# board_1.net
KiCad netlist of a schematic drawn in EAGLE
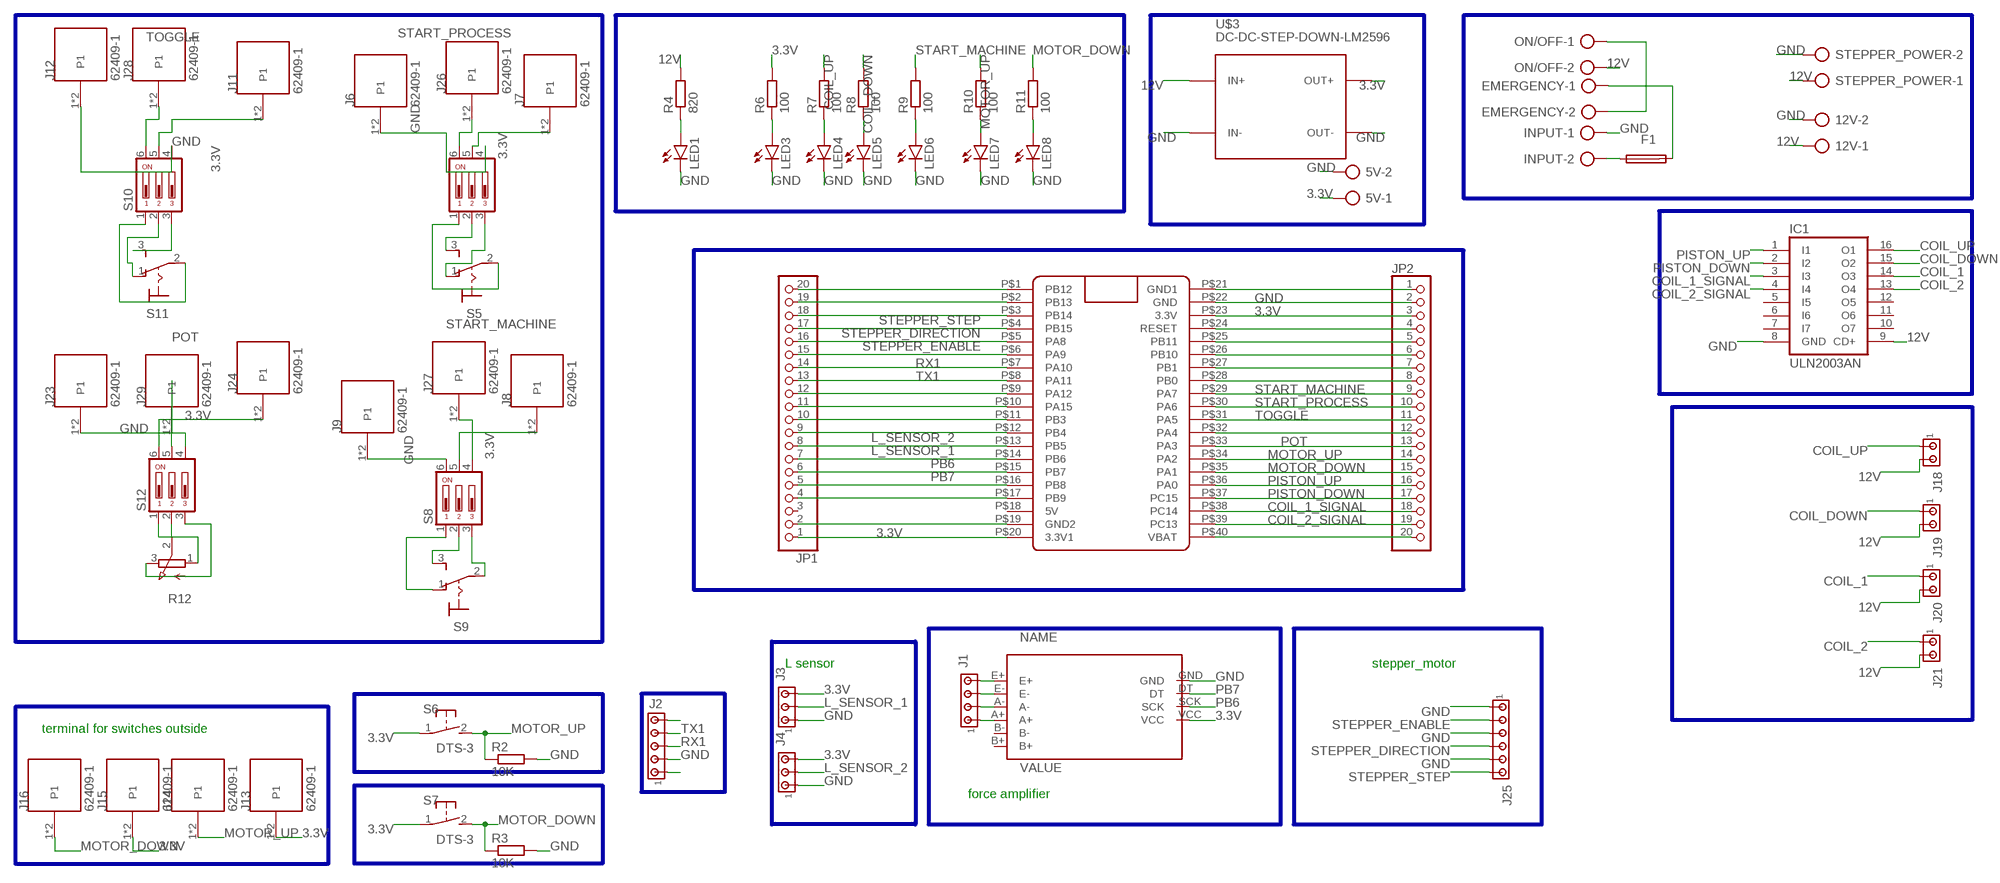
[diagram p0: schematic, sheet 1]

(export (version "E")
  (design (tool "Eeschema 10.0.6"))
  (components
    (comp (ref "5V")
      (value "AK300/2")
      (footprint "eagle-import:AK300_2")
      (libsource (lib "eagle-import") (part "AK300/2"))
    )
    (comp (ref "12V")
      (value "AK300/2")
      (footprint "eagle-import:AK300_2")
      (libsource (lib "eagle-import") (part "AK300/2"))
    )
    (comp (ref "EMERGENCY")
      (value "AK300/2")
      (footprint "eagle-import:AK300_2")
      (libsource (lib "eagle-import") (part "AK300/2"))
    )
    (comp (ref "F1")
      (value "SH22")
      (footprint "eagle-import:SH22")
      (libsource (lib "eagle-import") (part "SH22"))
    )
    (comp (ref "IC1")
      (value "ULN2003AN")
      (footprint "eagle-import:DIL16")
      (libsource (lib "eagle-import") (part "ULN2003AN"))
    )
    (comp (ref "INPUT")
      (value "AK300/2")
      (footprint "eagle-import:AK300_2")
      (libsource (lib "eagle-import") (part "AK300/2"))
    )
    (comp (ref "J1")
      (value "MTA04-100")
      (footprint "eagle-import:10X04MTA")
      (libsource (lib "eagle-import") (part "MTA04-100"))
    )
    (comp (ref "J2")
      (value "MTA05-100")
      (footprint "eagle-import:10X05MTA")
      (libsource (lib "eagle-import") (part "MTA05-100"))
    )
    (comp (ref "J3")
      (value "MTA03-100")
      (footprint "eagle-import:10X03MTA")
      (libsource (lib "eagle-import") (part "MTA03-100"))
    )
    (comp (ref "J4")
      (value "MTA03-100")
      (footprint "eagle-import:10X03MTA")
      (libsource (lib "eagle-import") (part "MTA03-100"))
    )
    (comp (ref "J6")
      (value "62409-1")
      (footprint "eagle-import:TE_62409-1")
      (fields (field (name "MF") "TE Connectivity"))
      (libsource (lib "eagle-import") (part "62409-1"))
    )
    (comp (ref "J7")
      (value "62409-1")
      (footprint "eagle-import:TE_62409-1")
      (fields (field (name "MF") "TE Connectivity"))
      (libsource (lib "eagle-import") (part "62409-1"))
    )
    (comp (ref "J8")
      (value "62409-1")
      (footprint "eagle-import:TE_62409-1")
      (fields (field (name "MF") "TE Connectivity"))
      (libsource (lib "eagle-import") (part "62409-1"))
    )
    (comp (ref "J9")
      (value "62409-1")
      (footprint "eagle-import:TE_62409-1")
      (fields (field (name "MF") "TE Connectivity"))
      (libsource (lib "eagle-import") (part "62409-1"))
    )
    (comp (ref "J11")
      (value "62409-1")
      (footprint "eagle-import:TE_62409-1")
      (fields (field (name "MF") "TE Connectivity"))
      (libsource (lib "eagle-import") (part "62409-1"))
    )
    (comp (ref "J12")
      (value "62409-1")
      (footprint "eagle-import:TE_62409-1")
      (fields (field (name "MF") "TE Connectivity"))
      (libsource (lib "eagle-import") (part "62409-1"))
    )
    (comp (ref "J13")
      (value "62409-1")
      (footprint "eagle-import:TE_62409-1")
      (fields (field (name "MF") "TE Connectivity"))
      (libsource (lib "eagle-import") (part "62409-1"))
    )
    (comp (ref "J14")
      (value "62409-1")
      (footprint "eagle-import:TE_62409-1")
      (fields (field (name "MF") "TE Connectivity"))
      (libsource (lib "eagle-import") (part "62409-1"))
    )
    (comp (ref "J15")
      (value "62409-1")
      (footprint "eagle-import:TE_62409-1")
      (fields (field (name "MF") "TE Connectivity"))
      (libsource (lib "eagle-import") (part "62409-1"))
    )
    (comp (ref "J16")
      (value "62409-1")
      (footprint "eagle-import:TE_62409-1")
      (fields (field (name "MF") "TE Connectivity"))
      (libsource (lib "eagle-import") (part "62409-1"))
    )
    (comp (ref "J18")
      (value "MTA02-100")
      (footprint "eagle-import:10X02MTA")
      (libsource (lib "eagle-import") (part "MTA02-100"))
    )
    (comp (ref "J19")
      (value "MTA02-100")
      (footprint "eagle-import:10X02MTA")
      (libsource (lib "eagle-import") (part "MTA02-100"))
    )
    (comp (ref "J20")
      (value "MTA02-100")
      (footprint "eagle-import:10X02MTA")
      (libsource (lib "eagle-import") (part "MTA02-100"))
    )
    (comp (ref "J21")
      (value "MTA02-100")
      (footprint "eagle-import:10X02MTA")
      (libsource (lib "eagle-import") (part "MTA02-100"))
    )
    (comp (ref "J23")
      (value "62409-1")
      (footprint "eagle-import:TE_62409-1")
      (fields (field (name "MF") "TE Connectivity"))
      (libsource (lib "eagle-import") (part "62409-1"))
    )
    (comp (ref "J24")
      (value "62409-1")
      (footprint "eagle-import:TE_62409-1")
      (fields (field (name "MF") "TE Connectivity"))
      (libsource (lib "eagle-import") (part "62409-1"))
    )
    (comp (ref "J25")
      (value "MTA06-100")
      (footprint "eagle-import:10X06MTA")
      (libsource (lib "eagle-import") (part "MTA06-100"))
    )
    (comp (ref "J26")
      (value "62409-1")
      (footprint "eagle-import:TE_62409-1")
      (fields (field (name "MF") "TE Connectivity"))
      (libsource (lib "eagle-import") (part "62409-1"))
    )
    (comp (ref "J27")
      (value "62409-1")
      (footprint "eagle-import:TE_62409-1")
      (fields (field (name "MF") "TE Connectivity"))
      (libsource (lib "eagle-import") (part "62409-1"))
    )
    (comp (ref "J28")
      (value "62409-1")
      (footprint "eagle-import:TE_62409-1")
      (fields (field (name "MF") "TE Connectivity"))
      (libsource (lib "eagle-import") (part "62409-1"))
    )
    (comp (ref "J29")
      (value "62409-1")
      (footprint "eagle-import:TE_62409-1")
      (fields (field (name "MF") "TE Connectivity"))
      (libsource (lib "eagle-import") (part "62409-1"))
    )
    (comp (ref "JP1")
      (value "PINHD-1X20")
      (footprint "eagle-import:1X20")
      (libsource (lib "eagle-import") (part "PINHD-1X20"))
    )
    (comp (ref "JP2")
      (value "PINHD-1X20")
      (footprint "eagle-import:1X20")
      (libsource (lib "eagle-import") (part "PINHD-1X20"))
    )
    (comp (ref "LED1")
      (value "LED3MM")
      (footprint "eagle-import:LED3MM")
      (libsource (lib "eagle-import") (part "LED3MM"))
    )
    (comp (ref "LED3")
      (value "LED3MM")
      (footprint "eagle-import:LED3MM")
      (libsource (lib "eagle-import") (part "LED3MM"))
    )
    (comp (ref "LED4")
      (value "LED3MM")
      (footprint "eagle-import:LED3MM")
      (libsource (lib "eagle-import") (part "LED3MM"))
    )
    (comp (ref "LED5")
      (value "LED3MM")
      (footprint "eagle-import:LED3MM")
      (libsource (lib "eagle-import") (part "LED3MM"))
    )
    (comp (ref "LED6")
      (value "LED3MM")
      (footprint "eagle-import:LED3MM")
      (libsource (lib "eagle-import") (part "LED3MM"))
    )
    (comp (ref "LED7")
      (value "LED3MM")
      (footprint "eagle-import:LED3MM")
      (libsource (lib "eagle-import") (part "LED3MM"))
    )
    (comp (ref "LED8")
      (value "LED3MM")
      (footprint "eagle-import:LED3MM")
      (libsource (lib "eagle-import") (part "LED3MM"))
    )
    (comp (ref "ON/OFF")
      (value "AK300/2")
      (footprint "eagle-import:AK300_2")
      (libsource (lib "eagle-import") (part "AK300/2"))
    )
    (comp (ref "R2")
      (value "10K")
      (footprint "eagle-import:0204_7")
      (libsource (lib "eagle-import") (part "R-EU_0204/7"))
    )
    (comp (ref "R3")
      (value "10K")
      (footprint "eagle-import:0204_7")
      (libsource (lib "eagle-import") (part "R-EU_0204/7"))
    )
    (comp (ref "R4")
      (value "820")
      (footprint "eagle-import:0204_7")
      (libsource (lib "eagle-import") (part "R-EU_0204/7"))
    )
    (comp (ref "R6")
      (value "100")
      (footprint "eagle-import:0204_7")
      (libsource (lib "eagle-import") (part "R-EU_0204/7"))
    )
    (comp (ref "R7")
      (value "100")
      (footprint "eagle-import:0204_7")
      (libsource (lib "eagle-import") (part "R-EU_0204/7"))
    )
    (comp (ref "R8")
      (value "100")
      (footprint "eagle-import:0204_7")
      (libsource (lib "eagle-import") (part "R-EU_0204/7"))
    )
    (comp (ref "R9")
      (value "100")
      (footprint "eagle-import:0204_7")
      (libsource (lib "eagle-import") (part "R-EU_0204/7"))
    )
    (comp (ref "R10")
      (value "100")
      (footprint "eagle-import:0204_7")
      (libsource (lib "eagle-import") (part "R-EU_0204/7"))
    )
    (comp (ref "R11")
      (value "100")
      (footprint "eagle-import:0204_7")
      (libsource (lib "eagle-import") (part "R-EU_0204/7"))
    )
    (comp (ref "R12")
      (value "3RP/1610N")
      (footprint "eagle-import:3RP_1610N")
      (libsource (lib "eagle-import") (part "3RP/1610N"))
    )
    (comp (ref "S4")
      (value "DP03")
      (footprint "eagle-import:DP-03")
      (fields (field (name "MPN") "MCDP03"))
      (libsource (lib "eagle-import") (part "DP03"))
    )
    (comp (ref "S5")
      (value "320-916")
      (footprint "eagle-import:320-916")
      (libsource (lib "eagle-import") (part "320-916"))
    )
    (comp (ref "S6")
      (value "DTS-3")
      (footprint "eagle-import:DTS-3")
      (libsource (lib "eagle-import") (part "DTS-3"))
    )
    (comp (ref "S7")
      (value "DTS-3")
      (footprint "eagle-import:DTS-3")
      (libsource (lib "eagle-import") (part "DTS-3"))
    )
    (comp (ref "S8")
      (value "DP03")
      (footprint "eagle-import:DP-03")
      (fields (field (name "MPN") "MCDP03"))
      (libsource (lib "eagle-import") (part "DP03"))
    )
    (comp (ref "S9")
      (value "320-916")
      (footprint "eagle-import:320-916")
      (libsource (lib "eagle-import") (part "320-916"))
    )
    (comp (ref "S10")
      (value "DP03")
      (footprint "eagle-import:DP-03")
      (fields (field (name "MPN") "MCDP03"))
      (libsource (lib "eagle-import") (part "DP03"))
    )
    (comp (ref "S11")
      (value "320-916")
      (footprint "eagle-import:320-916")
      (libsource (lib "eagle-import") (part "320-916"))
    )
    (comp (ref "S12")
      (value "DP03")
      (footprint "eagle-import:DP-03")
      (fields (field (name "MPN") "MCDP03"))
      (libsource (lib "eagle-import") (part "DP03"))
    )
    (comp (ref "STEPPER_POWER")
      (value "AK300/2")
      (footprint "eagle-import:AK300_2")
      (libsource (lib "eagle-import") (part "AK300/2"))
    )
    (comp (ref "U$1")
      (value "BLUE_PILL")
      (footprint "eagle-import:BLUE_PILL")
      (libsource (lib "eagle-import") (part "BLUE_PILL"))
    )
    (comp (ref "U$2")
      (value "HX711A")
      (footprint "eagle-import:HX711")
      (libsource (lib "eagle-import") (part "HX711A"))
    )
    (comp (ref "U$3")
      (value "DC-DC-STEP-DOWN-LM2596")
      (footprint "eagle-import:DC-DC-STEP-DOWN-LM2596")
      (libsource (lib "eagle-import") (part "DC-DC-STEP-DOWN-LM2596"))
    )
  )
  (nets
    (net (code "1") (name "/3.3V") (class "Default")
      (node (ref "5V") (pin "1") (pinfunction "KL_1") (pintype "passive"))
      (node (ref "J11") (pin "1") (pinfunction "P1_1") (pintype "passive"))
      (node (ref "J11") (pin "2") (pinfunction "P1_2") (pintype "passive"))
      (node (ref "J13") (pin "1") (pinfunction "P1_1") (pintype "passive"))
      (node (ref "J13") (pin "2") (pinfunction "P1_2") (pintype "passive"))
      (node (ref "J15") (pin "1") (pinfunction "P1_1") (pintype "passive"))
      (node (ref "J15") (pin "2") (pinfunction "P1_2") (pintype "passive"))
      (node (ref "J24") (pin "1") (pinfunction "P1_1") (pintype "passive"))
      (node (ref "J24") (pin "2") (pinfunction "P1_2") (pintype "passive"))
      (node (ref "J3") (pin "3") (pinfunction "3_3") (pintype "passive"))
      (node (ref "J4") (pin "3") (pinfunction "3_3") (pintype "passive"))
      (node (ref "J7") (pin "1") (pinfunction "P1_1") (pintype "passive"))
      (node (ref "J7") (pin "2") (pinfunction "P1_2") (pintype "passive"))
      (node (ref "J8") (pin "1") (pinfunction "P1_1") (pintype "passive"))
      (node (ref "J8") (pin "2") (pinfunction "P1_2") (pintype "passive"))
      (node (ref "JP1") (pin "1") (pinfunction "1_1") (pintype "passive"))
      (node (ref "JP2") (pin "3") (pinfunction "3_3") (pintype "passive"))
      (node (ref "R6") (pin "2") (pinfunction "2_2") (pintype "passive"))
      (node (ref "S10") (pin "5") (pinfunction "5_5") (pintype "passive"))
      (node (ref "S12") (pin "6") (pinfunction "6_6") (pintype "passive"))
      (node (ref "S4") (pin "5") (pinfunction "5_5") (pintype "passive"))
      (node (ref "S6") (pin "1") (pinfunction "1_1") (pintype "passive"))
      (node (ref "S7") (pin "1") (pinfunction "1_1") (pintype "passive"))
      (node (ref "S8") (pin "5") (pinfunction "5_5") (pintype "passive"))
      (node (ref "U$1") (pin "P$20") (pinfunction "3.3V1_P$20") (pintype "bidirectional"))
      (node (ref "U$1") (pin "P$23") (pinfunction "3.3V_P$23") (pintype "bidirectional"))
      (node (ref "U$2") (pin "VCC") (pinfunction "VCC_VCC") (pintype "bidirectional"))
      (node (ref "U$3") (pin "OUT+") (pinfunction "OUT+_OUT+") (pintype "bidirectional"))
    )
    (net (code "2") (name "/12V") (class "Default")
      (node (ref "12V") (pin "1") (pinfunction "KL_1") (pintype "passive"))
      (node (ref "IC1") (pin "9") (pinfunction "CD+_9") (pintype "passive"))
      (node (ref "J18") (pin "2") (pinfunction "2_2") (pintype "passive"))
      (node (ref "J19") (pin "2") (pinfunction "2_2") (pintype "passive"))
      (node (ref "J20") (pin "2") (pinfunction "2_2") (pintype "passive"))
      (node (ref "J21") (pin "2") (pinfunction "2_2") (pintype "passive"))
      (node (ref "ON/OFF") (pin "2") (pinfunction "KL_2") (pintype "passive"))
      (node (ref "R4") (pin "2") (pinfunction "2_2") (pintype "passive"))
      (node (ref "STEPPER_POWER") (pin "1") (pinfunction "KL_1") (pintype "passive"))
      (node (ref "U$3") (pin "IN+") (pinfunction "IN+_IN+") (pintype "bidirectional"))
    )
    (net (code "3") (name "/COIL_1") (class "Default")
      (node (ref "IC1") (pin "14") (pinfunction "O3_14") (pintype "open_collector"))
      (node (ref "J20") (pin "1") (pinfunction "1_1") (pintype "passive"))
    )
    (net (code "4") (name "/COIL_1_SIGNAL") (class "Default")
      (node (ref "IC1") (pin "3") (pinfunction "I3_3") (pintype "input"))
      (node (ref "JP2") (pin "18") (pinfunction "18_18") (pintype "passive"))
      (node (ref "U$1") (pin "P$38") (pinfunction "PC14_P$38") (pintype "bidirectional"))
    )
    (net (code "5") (name "/COIL_2") (class "Default")
      (node (ref "IC1") (pin "13") (pinfunction "O4_13") (pintype "open_collector"))
      (node (ref "J21") (pin "1") (pinfunction "1_1") (pintype "passive"))
    )
    (net (code "6") (name "/COIL_2_SIGNAL") (class "Default")
      (node (ref "IC1") (pin "4") (pinfunction "I4_4") (pintype "input"))
      (node (ref "JP2") (pin "19") (pinfunction "19_19") (pintype "passive"))
      (node (ref "U$1") (pin "P$39") (pinfunction "PC13_P$39") (pintype "bidirectional"))
    )
    (net (code "7") (name "/COIL_DOWN") (class "Default")
      (node (ref "IC1") (pin "15") (pinfunction "O2_15") (pintype "open_collector"))
      (node (ref "J19") (pin "1") (pinfunction "1_1") (pintype "passive"))
      (node (ref "R8") (pin "2") (pinfunction "2_2") (pintype "passive"))
    )
    (net (code "8") (name "/COIL_UP") (class "Default")
      (node (ref "IC1") (pin "16") (pinfunction "O1_16") (pintype "open_collector"))
      (node (ref "J18") (pin "1") (pinfunction "1_1") (pintype "passive"))
      (node (ref "R7") (pin "2") (pinfunction "2_2") (pintype "passive"))
    )
    (net (code "9") (name "/GND") (class "Default")
      (node (ref "12V") (pin "2") (pinfunction "KL_2") (pintype "passive"))
      (node (ref "5V") (pin "2") (pinfunction "KL_2") (pintype "passive"))
      (node (ref "IC1") (pin "8") (pinfunction "GND_8") (pintype "power_in"))
      (node (ref "INPUT") (pin "1") (pinfunction "KL_1") (pintype "passive"))
      (node (ref "J12") (pin "1") (pinfunction "P1_1") (pintype "passive"))
      (node (ref "J12") (pin "2") (pinfunction "P1_2") (pintype "passive"))
      (node (ref "J2") (pin "2") (pinfunction "2_2") (pintype "passive"))
      (node (ref "J23") (pin "1") (pinfunction "P1_1") (pintype "passive"))
      (node (ref "J23") (pin "2") (pinfunction "P1_2") (pintype "passive"))
      (node (ref "J25") (pin "1") (pinfunction "1_1") (pintype "passive"))
      (node (ref "J25") (pin "3") (pinfunction "3_3") (pintype "passive"))
      (node (ref "J25") (pin "5") (pinfunction "5_5") (pintype "passive"))
      (node (ref "J3") (pin "1") (pinfunction "1_1") (pintype "passive"))
      (node (ref "J4") (pin "1") (pinfunction "1_1") (pintype "passive"))
      (node (ref "J6") (pin "1") (pinfunction "P1_1") (pintype "passive"))
      (node (ref "J6") (pin "2") (pinfunction "P1_2") (pintype "passive"))
      (node (ref "J9") (pin "1") (pinfunction "P1_1") (pintype "passive"))
      (node (ref "J9") (pin "2") (pinfunction "P1_2") (pintype "passive"))
      (node (ref "JP1") (pin "2") (pinfunction "2_2") (pintype "passive"))
      (node (ref "JP2") (pin "2") (pinfunction "2_2") (pintype "passive"))
      (node (ref "LED1") (pin "K") (pinfunction "C_K") (pintype "passive"))
      (node (ref "LED3") (pin "K") (pinfunction "C_K") (pintype "passive"))
      (node (ref "LED4") (pin "K") (pinfunction "C_K") (pintype "passive"))
      (node (ref "LED5") (pin "K") (pinfunction "C_K") (pintype "passive"))
      (node (ref "LED6") (pin "K") (pinfunction "C_K") (pintype "passive"))
      (node (ref "LED7") (pin "K") (pinfunction "C_K") (pintype "passive"))
      (node (ref "LED8") (pin "K") (pinfunction "C_K") (pintype "passive"))
      (node (ref "R2") (pin "2") (pinfunction "2_2") (pintype "passive"))
      (node (ref "R3") (pin "2") (pinfunction "2_2") (pintype "passive"))
      (node (ref "S10") (pin "4") (pinfunction "4_4") (pintype "passive"))
      (node (ref "S12") (pin "4") (pinfunction "4_4") (pintype "passive"))
      (node (ref "S4") (pin "4") (pinfunction "4_4") (pintype "passive"))
      (node (ref "S8") (pin "6") (pinfunction "6_6") (pintype "passive"))
      (node (ref "STEPPER_POWER") (pin "2") (pinfunction "KL_2") (pintype "passive"))
      (node (ref "U$1") (pin "P$19") (pinfunction "GND2_P$19") (pintype "bidirectional"))
      (node (ref "U$1") (pin "P$22") (pinfunction "GND_P$22") (pintype "bidirectional"))
      (node (ref "U$2") (pin "GND") (pinfunction "GND_GND") (pintype "bidirectional"))
      (node (ref "U$3") (pin "IN-") (pinfunction "IN-_IN-") (pintype "bidirectional"))
      (node (ref "U$3") (pin "OUT-") (pinfunction "OUT-_OUT-") (pintype "bidirectional"))
    )
    (net (code "10") (name "/L_SENSOR_1") (class "Default")
      (node (ref "J3") (pin "2") (pinfunction "2_2") (pintype "passive"))
      (node (ref "JP1") (pin "8") (pinfunction "8_8") (pintype "passive"))
      (node (ref "U$1") (pin "P$13") (pinfunction "PB5_P$13") (pintype "bidirectional"))
    )
    (net (code "11") (name "/L_SENSOR_2") (class "Default")
      (node (ref "J4") (pin "2") (pinfunction "2_2") (pintype "passive"))
      (node (ref "JP1") (pin "9") (pinfunction "9_9") (pintype "passive"))
      (node (ref "U$1") (pin "P$12") (pinfunction "PB4_P$12") (pintype "bidirectional"))
    )
    (net (code "12") (name "/MOTOR_DOWN") (class "Default")
      (node (ref "J16") (pin "1") (pinfunction "P1_1") (pintype "passive"))
      (node (ref "J16") (pin "2") (pinfunction "P1_2") (pintype "passive"))
      (node (ref "JP2") (pin "15") (pinfunction "15_15") (pintype "passive"))
      (node (ref "R11") (pin "2") (pinfunction "2_2") (pintype "passive"))
      (node (ref "R3") (pin "1") (pinfunction "1_1") (pintype "passive"))
      (node (ref "S7") (pin "2") (pinfunction "2_2") (pintype "passive"))
      (node (ref "U$1") (pin "P$35") (pinfunction "PA1_P$35") (pintype "bidirectional"))
    )
    (net (code "13") (name "/MOTOR_UP") (class "Default")
      (node (ref "J14") (pin "1") (pinfunction "P1_1") (pintype "passive"))
      (node (ref "J14") (pin "2") (pinfunction "P1_2") (pintype "passive"))
      (node (ref "JP2") (pin "14") (pinfunction "14_14") (pintype "passive"))
      (node (ref "R10") (pin "2") (pinfunction "2_2") (pintype "passive"))
      (node (ref "R2") (pin "1") (pinfunction "1_1") (pintype "passive"))
      (node (ref "S6") (pin "2") (pinfunction "2_2") (pintype "passive"))
      (node (ref "U$1") (pin "P$34") (pinfunction "PA2_P$34") (pintype "bidirectional"))
    )
    (net (code "14") (name "/PB6") (class "Default")
      (node (ref "JP1") (pin "7") (pinfunction "7_7") (pintype "passive"))
      (node (ref "U$1") (pin "P$14") (pinfunction "PB6_P$14") (pintype "bidirectional"))
      (node (ref "U$2") (pin "SCK") (pinfunction "SCK_SCK") (pintype "bidirectional"))
    )
    (net (code "15") (name "/PB7") (class "Default")
      (node (ref "JP1") (pin "6") (pinfunction "6_6") (pintype "passive"))
      (node (ref "U$1") (pin "P$15") (pinfunction "PB7_P$15") (pintype "bidirectional"))
      (node (ref "U$2") (pin "DT") (pinfunction "DT_DT") (pintype "bidirectional"))
    )
    (net (code "16") (name "/PISTON_DOWN") (class "Default")
      (node (ref "IC1") (pin "2") (pinfunction "I2_2") (pintype "input"))
      (node (ref "JP2") (pin "17") (pinfunction "17_17") (pintype "passive"))
      (node (ref "U$1") (pin "P$37") (pinfunction "PC15_P$37") (pintype "bidirectional"))
    )
    (net (code "17") (name "/PISTON_UP") (class "Default")
      (node (ref "IC1") (pin "1") (pinfunction "I1_1") (pintype "input"))
      (node (ref "JP2") (pin "16") (pinfunction "16_16") (pintype "passive"))
      (node (ref "U$1") (pin "P$36") (pinfunction "PA0_P$36") (pintype "bidirectional"))
    )
    (net (code "18") (name "/POT") (class "Default")
      (node (ref "J29") (pin "1") (pinfunction "P1_1") (pintype "passive"))
      (node (ref "J29") (pin "2") (pinfunction "P1_2") (pintype "passive"))
      (node (ref "JP2") (pin "13") (pinfunction "13_13") (pintype "passive"))
      (node (ref "S12") (pin "5") (pinfunction "5_5") (pintype "passive"))
      (node (ref "U$1") (pin "P$33") (pinfunction "PA3_P$33") (pintype "bidirectional"))
    )
    (net (code "19") (name "/RX1") (class "Default")
      (node (ref "J2") (pin "3") (pinfunction "3_3") (pintype "passive"))
      (node (ref "JP1") (pin "15") (pinfunction "15_15") (pintype "passive"))
      (node (ref "U$1") (pin "P$6") (pinfunction "PA9_P$6") (pintype "bidirectional"))
    )
    (net (code "20") (name "/START_MACHINE") (class "Default")
      (node (ref "J27") (pin "1") (pinfunction "P1_1") (pintype "passive"))
      (node (ref "J27") (pin "2") (pinfunction "P1_2") (pintype "passive"))
      (node (ref "JP2") (pin "9") (pinfunction "9_9") (pintype "passive"))
      (node (ref "R9") (pin "2") (pinfunction "2_2") (pintype "passive"))
      (node (ref "S8") (pin "4") (pinfunction "4_4") (pintype "passive"))
      (node (ref "U$1") (pin "P$29") (pinfunction "PA7_P$29") (pintype "bidirectional"))
    )
    (net (code "21") (name "/START_PROCESS") (class "Default")
      (node (ref "J26") (pin "1") (pinfunction "P1_1") (pintype "passive"))
      (node (ref "J26") (pin "2") (pinfunction "P1_2") (pintype "passive"))
      (node (ref "JP2") (pin "10") (pinfunction "10_10") (pintype "passive"))
      (node (ref "S4") (pin "6") (pinfunction "6_6") (pintype "passive"))
      (node (ref "U$1") (pin "P$30") (pinfunction "PA6_P$30") (pintype "bidirectional"))
    )
    (net (code "22") (name "/STEPPER_DIRECTION") (class "Default")
      (node (ref "J25") (pin "4") (pinfunction "4_4") (pintype "passive"))
      (node (ref "JP1") (pin "17") (pinfunction "17_17") (pintype "passive"))
      (node (ref "U$1") (pin "P$4") (pinfunction "PB15_P$4") (pintype "bidirectional"))
    )
    (net (code "23") (name "/STEPPER_ENABLE") (class "Default")
      (node (ref "J25") (pin "2") (pinfunction "2_2") (pintype "passive"))
      (node (ref "JP1") (pin "16") (pinfunction "16_16") (pintype "passive"))
      (node (ref "U$1") (pin "P$5") (pinfunction "PA8_P$5") (pintype "bidirectional"))
    )
    (net (code "24") (name "/STEPPER_STEP") (class "Default")
      (node (ref "J25") (pin "6") (pinfunction "6_6") (pintype "passive"))
      (node (ref "JP1") (pin "18") (pinfunction "18_18") (pintype "passive"))
      (node (ref "U$1") (pin "P$3") (pinfunction "PB14_P$3") (pintype "bidirectional"))
    )
    (net (code "25") (name "/TOGGLE") (class "Default")
      (node (ref "J28") (pin "1") (pinfunction "P1_1") (pintype "passive"))
      (node (ref "J28") (pin "2") (pinfunction "P1_2") (pintype "passive"))
      (node (ref "JP2") (pin "11") (pinfunction "11_11") (pintype "passive"))
      (node (ref "S10") (pin "6") (pinfunction "6_6") (pintype "passive"))
      (node (ref "U$1") (pin "P$31") (pinfunction "PA5_P$31") (pintype "bidirectional"))
    )
    (net (code "26") (name "/TX1") (class "Default")
      (node (ref "J2") (pin "4") (pinfunction "4_4") (pintype "passive"))
      (node (ref "JP1") (pin "14") (pinfunction "14_14") (pintype "passive"))
      (node (ref "U$1") (pin "P$7") (pinfunction "PA10_P$7") (pintype "bidirectional"))
    )
    (net (code "27") (name "Net-(EMERGENCYA-KL)") (class "Default")
      (node (ref "EMERGENCY") (pin "1") (pinfunction "KL_1") (pintype "passive"))
      (node (ref "F1") (pin "2") (pinfunction "2_2") (pintype "passive"))
    )
    (net (code "28") (name "Net-(EMERGENCYB-KL)") (class "Default")
      (node (ref "EMERGENCY") (pin "2") (pinfunction "KL_2") (pintype "passive"))
      (node (ref "ON/OFF") (pin "1") (pinfunction "KL_1") (pintype "passive"))
    )
    (net (code "29") (name "Net-(INPUTB-KL)") (class "Default")
      (node (ref "F1") (pin "1") (pinfunction "1_1") (pintype "passive"))
      (node (ref "INPUT") (pin "2") (pinfunction "KL_2") (pintype "passive"))
    )
    (net (code "30") (name "Net-(J1-Pad1)") (class "Default")
      (node (ref "J1") (pin "1") (pinfunction "1_1") (pintype "passive"))
      (node (ref "U$2") (pin "A+") (pinfunction "A+_A+") (pintype "bidirectional"))
    )
    (net (code "31") (name "Net-(J1-Pad2)") (class "Default")
      (node (ref "J1") (pin "2") (pinfunction "2_2") (pintype "passive"))
      (node (ref "U$2") (pin "A-") (pinfunction "A-_A-") (pintype "bidirectional"))
    )
    (net (code "32") (name "Net-(J1-Pad3)") (class "Default")
      (node (ref "J1") (pin "3") (pinfunction "3_3") (pintype "passive"))
      (node (ref "U$2") (pin "E-") (pinfunction "E-_E-") (pintype "bidirectional"))
    )
    (net (code "33") (name "Net-(J1-Pad4)") (class "Default")
      (node (ref "J1") (pin "4") (pinfunction "4_4") (pintype "passive"))
      (node (ref "U$2") (pin "E+") (pinfunction "E+_E+") (pintype "bidirectional"))
    )
    (net (code "34") (name "Net-(LED1-PadA)") (class "Default")
      (node (ref "LED1") (pin "A") (pinfunction "A_A") (pintype "passive"))
      (node (ref "R4") (pin "1") (pinfunction "1_1") (pintype "passive"))
    )
    (net (code "35") (name "Net-(LED3-PadA)") (class "Default")
      (node (ref "LED3") (pin "A") (pinfunction "A_A") (pintype "passive"))
      (node (ref "R6") (pin "1") (pinfunction "1_1") (pintype "passive"))
    )
    (net (code "36") (name "Net-(LED4-PadA)") (class "Default")
      (node (ref "LED4") (pin "A") (pinfunction "A_A") (pintype "passive"))
      (node (ref "R7") (pin "1") (pinfunction "1_1") (pintype "passive"))
    )
    (net (code "37") (name "Net-(LED5-PadA)") (class "Default")
      (node (ref "LED5") (pin "A") (pinfunction "A_A") (pintype "passive"))
      (node (ref "R8") (pin "1") (pinfunction "1_1") (pintype "passive"))
    )
    (net (code "38") (name "Net-(LED6-PadA)") (class "Default")
      (node (ref "LED6") (pin "A") (pinfunction "A_A") (pintype "passive"))
      (node (ref "R9") (pin "1") (pinfunction "1_1") (pintype "passive"))
    )
    (net (code "39") (name "Net-(LED7-PadA)") (class "Default")
      (node (ref "LED7") (pin "A") (pinfunction "A_A") (pintype "passive"))
      (node (ref "R10") (pin "1") (pinfunction "1_1") (pintype "passive"))
    )
    (net (code "40") (name "Net-(LED8-PadA)") (class "Default")
      (node (ref "LED8") (pin "A") (pinfunction "A_A") (pintype "passive"))
      (node (ref "R11") (pin "1") (pinfunction "1_1") (pintype "passive"))
    )
    (net (code "41") (name "Net-(R12-A)") (class "Default")
      (node (ref "R12") (pin "1") (pinfunction "A_1") (pintype "passive"))
      (node (ref "S12") (pin "1") (pinfunction "1_1") (pintype "passive"))
    )
    (net (code "42") (name "Net-(R12-E)") (class "Default")
      (node (ref "R12") (pin "3") (pinfunction "E_3") (pintype "passive"))
      (node (ref "S12") (pin "3") (pinfunction "3_3") (pintype "passive"))
    )
    (net (code "43") (name "Net-(R12-S)") (class "Default")
      (node (ref "R12") (pin "2") (pinfunction "S_2") (pintype "passive"))
      (node (ref "S12") (pin "2") (pinfunction "2_2") (pintype "passive"))
    )
    (net (code "44") (name "Net-(S5-O)") (class "Default")
      (node (ref "S4") (pin "3") (pinfunction "3_3") (pintype "passive"))
      (node (ref "S5") (pin "1") (pinfunction "O_1") (pintype "passive"))
    )
    (net (code "45") (name "Net-(S5-P)") (class "Default")
      (node (ref "S4") (pin "1") (pinfunction "1_1") (pintype "passive"))
      (node (ref "S5") (pin "2") (pinfunction "P_2") (pintype "passive"))
    )
    (net (code "46") (name "Net-(S5-S)") (class "Default")
      (node (ref "S4") (pin "2") (pinfunction "2_2") (pintype "passive"))
      (node (ref "S5") (pin "3") (pinfunction "S_3") (pintype "passive"))
    )
    (net (code "47") (name "Net-(S9-O)") (class "Default")
      (node (ref "S8") (pin "1") (pinfunction "1_1") (pintype "passive"))
      (node (ref "S9") (pin "1") (pinfunction "O_1") (pintype "passive"))
    )
    (net (code "48") (name "Net-(S9-P)") (class "Default")
      (node (ref "S8") (pin "3") (pinfunction "3_3") (pintype "passive"))
      (node (ref "S9") (pin "2") (pinfunction "P_2") (pintype "passive"))
    )
    (net (code "49") (name "Net-(S9-S)") (class "Default")
      (node (ref "S8") (pin "2") (pinfunction "2_2") (pintype "passive"))
      (node (ref "S9") (pin "3") (pinfunction "S_3") (pintype "passive"))
    )
    (net (code "50") (name "Net-(S11-O)") (class "Default")
      (node (ref "S10") (pin "2") (pinfunction "2_2") (pintype "passive"))
      (node (ref "S11") (pin "1") (pinfunction "O_1") (pintype "passive"))
    )
    (net (code "51") (name "Net-(S11-P)") (class "Default")
      (node (ref "S10") (pin "1") (pinfunction "1_1") (pintype "passive"))
      (node (ref "S11") (pin "2") (pinfunction "P_2") (pintype "passive"))
    )
    (net (code "52") (name "Net-(S11-S)") (class "Default")
      (node (ref "S10") (pin "3") (pinfunction "3_3") (pintype "passive"))
      (node (ref "S11") (pin "3") (pinfunction "S_3") (pintype "passive"))
    )
    (net (code "53") (name "Net-(U$1-GND1)") (class "Default")
      (node (ref "JP2") (pin "1") (pinfunction "1_1") (pintype "passive"))
      (node (ref "U$1") (pin "P$21") (pinfunction "GND1_P$21") (pintype "power_in"))
    )
    (net (code "54") (name "Net-(U$1-PA4)") (class "Default")
      (node (ref "JP2") (pin "12") (pinfunction "12_12") (pintype "passive"))
      (node (ref "U$1") (pin "P$32") (pinfunction "PA4_P$32") (pintype "bidirectional"))
    )
    (net (code "55") (name "Net-(U$1-PA11)") (class "Default")
      (node (ref "JP1") (pin "13") (pinfunction "13_13") (pintype "passive"))
      (node (ref "U$1") (pin "P$8") (pinfunction "PA11_P$8") (pintype "bidirectional"))
    )
    (net (code "56") (name "Net-(U$1-PA12)") (class "Default")
      (node (ref "JP1") (pin "12") (pinfunction "12_12") (pintype "passive"))
      (node (ref "U$1") (pin "P$9") (pinfunction "PA12_P$9") (pintype "bidirectional"))
    )
    (net (code "57") (name "Net-(U$1-PA15)") (class "Default")
      (node (ref "JP1") (pin "11") (pinfunction "11_11") (pintype "passive"))
      (node (ref "U$1") (pin "P$10") (pinfunction "PA15_P$10") (pintype "bidirectional"))
    )
    (net (code "58") (name "Net-(U$1-PB0)") (class "Default")
      (node (ref "JP2") (pin "8") (pinfunction "8_8") (pintype "passive"))
      (node (ref "U$1") (pin "P$28") (pinfunction "PB0_P$28") (pintype "bidirectional"))
    )
    (net (code "59") (name "Net-(U$1-PB1)") (class "Default")
      (node (ref "JP2") (pin "7") (pinfunction "7_7") (pintype "passive"))
      (node (ref "U$1") (pin "P$27") (pinfunction "PB1_P$27") (pintype "bidirectional"))
    )
    (net (code "60") (name "Net-(U$1-PB3)") (class "Default")
      (node (ref "JP1") (pin "10") (pinfunction "10_10") (pintype "passive"))
      (node (ref "U$1") (pin "P$11") (pinfunction "PB3_P$11") (pintype "bidirectional"))
    )
    (net (code "61") (name "Net-(U$1-PB8)") (class "Default")
      (node (ref "JP1") (pin "5") (pinfunction "5_5") (pintype "passive"))
      (node (ref "U$1") (pin "P$16") (pinfunction "PB8_P$16") (pintype "bidirectional"))
    )
    (net (code "62") (name "Net-(U$1-PB9)") (class "Default")
      (node (ref "JP1") (pin "4") (pinfunction "4_4") (pintype "passive"))
      (node (ref "U$1") (pin "P$17") (pinfunction "PB9_P$17") (pintype "bidirectional"))
    )
    (net (code "63") (name "Net-(U$1-PB10)") (class "Default")
      (node (ref "JP2") (pin "6") (pinfunction "6_6") (pintype "passive"))
      (node (ref "U$1") (pin "P$26") (pinfunction "PB10_P$26") (pintype "bidirectional"))
    )
    (net (code "64") (name "Net-(U$1-PB11)") (class "Default")
      (node (ref "JP2") (pin "5") (pinfunction "5_5") (pintype "passive"))
      (node (ref "U$1") (pin "P$25") (pinfunction "PB11_P$25") (pintype "bidirectional"))
    )
    (net (code "65") (name "Net-(U$1-PB12)") (class "Default")
      (node (ref "JP1") (pin "20") (pinfunction "20_20") (pintype "passive"))
      (node (ref "U$1") (pin "P$1") (pinfunction "PB12_P$1") (pintype "bidirectional"))
    )
    (net (code "66") (name "Net-(U$1-PB13)") (class "Default")
      (node (ref "JP1") (pin "19") (pinfunction "19_19") (pintype "passive"))
      (node (ref "U$1") (pin "P$2") (pinfunction "PB13_P$2") (pintype "bidirectional"))
    )
    (net (code "67") (name "Net-(U$1-RESET)") (class "Default")
      (node (ref "JP2") (pin "4") (pinfunction "4_4") (pintype "passive"))
      (node (ref "U$1") (pin "P$24") (pinfunction "RESET_P$24") (pintype "bidirectional"))
    )
    (net (code "68") (name "Net-(U$1-VBAT)") (class "Default")
      (node (ref "JP2") (pin "20") (pinfunction "20_20") (pintype "passive"))
      (node (ref "U$1") (pin "P$40") (pinfunction "VBAT_P$40") (pintype "bidirectional"))
    )
    (net (code "69") (name "unconnected-(IC1-I5-Pad5)") (class "Default")
      (node (ref "IC1") (pin "5") (pinfunction "I5_5") (pintype "input"))
    )
    (net (code "70") (name "unconnected-(IC1-I6-Pad6)") (class "Default")
      (node (ref "IC1") (pin "6") (pinfunction "I6_6") (pintype "input"))
    )
    (net (code "71") (name "unconnected-(IC1-I7-Pad7)") (class "Default")
      (node (ref "IC1") (pin "7") (pinfunction "I7_7") (pintype "input"))
    )
    (net (code "72") (name "unconnected-(IC1-O5-Pad12)") (class "Default")
      (node (ref "IC1") (pin "12") (pinfunction "O5_12") (pintype "open_collector"))
    )
    (net (code "73") (name "unconnected-(IC1-O6-Pad11)") (class "Default")
      (node (ref "IC1") (pin "11") (pinfunction "O6_11") (pintype "open_collector"))
    )
    (net (code "74") (name "unconnected-(IC1-O7-Pad10)") (class "Default")
      (node (ref "IC1") (pin "10") (pinfunction "O7_10") (pintype "open_collector"))
    )
    (net (code "75") (name "unconnected-(J2-Pad1)") (class "Default")
      (node (ref "J2") (pin "1") (pinfunction "1_1") (pintype "passive"))
    )
    (net (code "76") (name "unconnected-(J2-Pad5)") (class "Default")
      (node (ref "J2") (pin "5") (pinfunction "5_5") (pintype "passive"))
    )
    (net (code "77") (name "unconnected-(JP1-Pad3)") (class "Default")
      (node (ref "JP1") (pin "3") (pinfunction "3_3") (pintype "passive"))
    )
    (net (code "78") (name "unconnected-(U$1-5V-PadP$18)") (class "Default")
      (node (ref "U$1") (pin "P$18") (pinfunction "5V_P$18") (pintype "bidirectional"))
    )
    (net (code "79") (name "unconnected-(U$2-PadB+)") (class "Default")
      (node (ref "U$2") (pin "B+") (pinfunction "B+_B+") (pintype "bidirectional"))
    )
    (net (code "80") (name "unconnected-(U$2-PadB-)") (class "Default")
      (node (ref "U$2") (pin "B-") (pinfunction "B-_B-") (pintype "bidirectional"))
    )
  )
)
